# msx_io_expander_slot.net
KiCad netlist of a schematic drawn in EAGLE
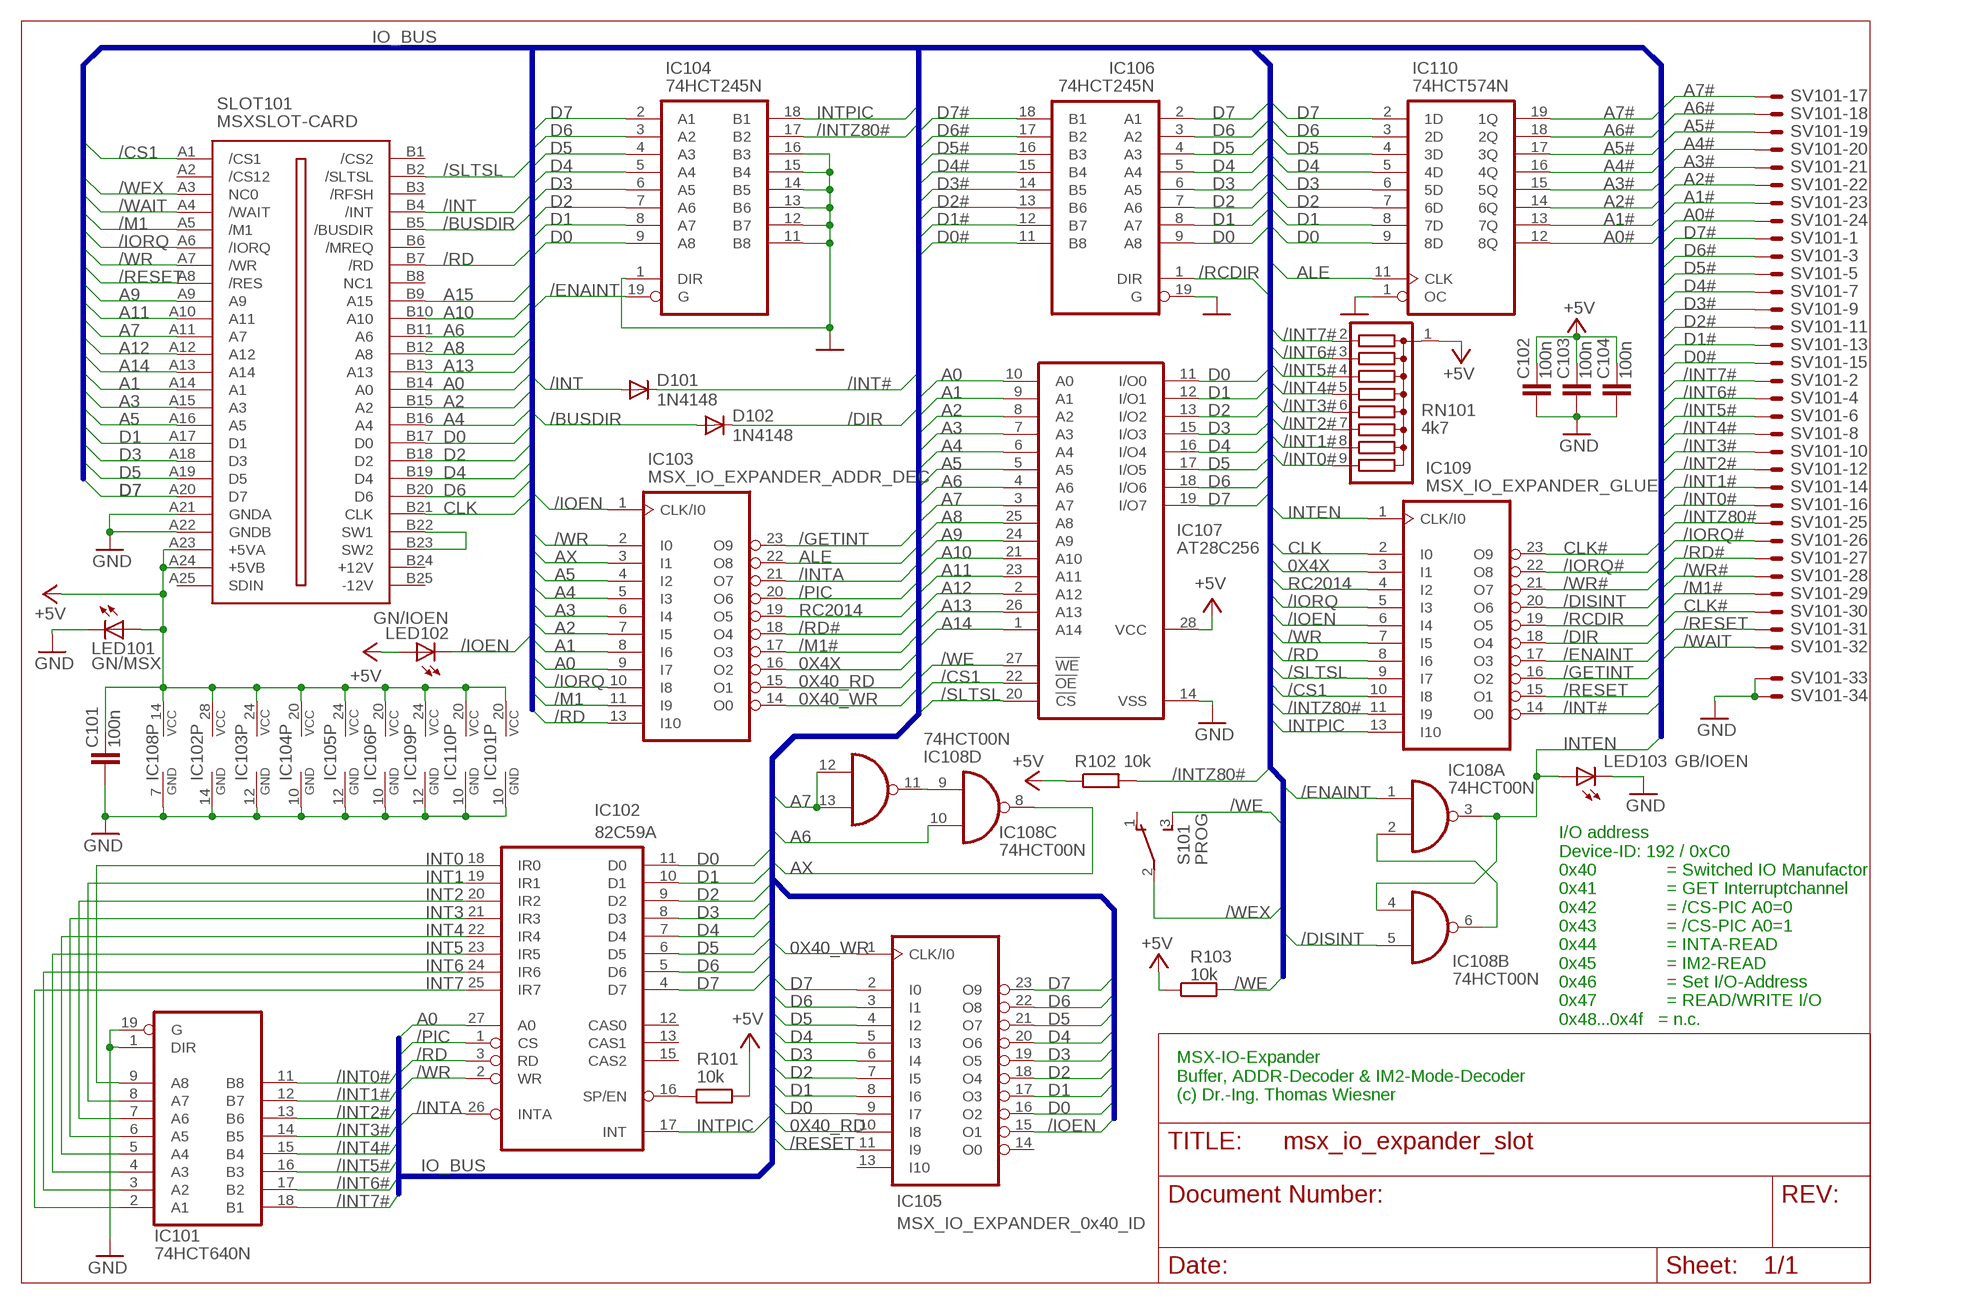
[diagram p0: schematic, sheet 1]

(export (version "E")
  (design (tool "Eeschema 10.0.6"))
  (components
    (comp (ref "C101")
      (value "100n")
      (footprint "eagle-import:C025-025X050")
      (libsource (lib "eagle-import") (part "C-EU025-025X050"))
    )
    (comp (ref "C102")
      (value "100n")
      (footprint "eagle-import:C025-025X050")
      (libsource (lib "eagle-import") (part "C-EU025-025X050"))
    )
    (comp (ref "C103")
      (value "100n")
      (footprint "eagle-import:C025-025X050")
      (libsource (lib "eagle-import") (part "C-EU025-025X050"))
    )
    (comp (ref "C104")
      (value "100n")
      (footprint "eagle-import:C025-025X050")
      (libsource (lib "eagle-import") (part "C-EU025-025X050"))
    )
    (comp (ref "D101")
      (value "1N4148")
      (footprint "eagle-import:DO35-10")
      (libsource (lib "eagle-import") (part "1N4148DO35-10"))
    )
    (comp (ref "D102")
      (value "1N4148")
      (footprint "eagle-import:DO35-10")
      (libsource (lib "eagle-import") (part "1N4148DO35-10"))
    )
    (comp (ref "IC101")
      (value "74HCT640N")
      (footprint "eagle-import:DIL20")
      (libsource (lib "eagle-import") (part "74245NHCT"))
    )
    (comp (ref "IC102")
      (value "82C59A")
      (footprint "eagle-import:DIL28-6")
      (libsource (lib "eagle-import") (part "8259A"))
    )
    (comp (ref "IC103")
      (value "MSX_IO_EXPANDER_ADDR_DEC")
      (footprint "eagle-import:DIL24-3")
      (fields (field (name "MPN") "GAL22V10D-7LPN"))
      (libsource (lib "eagle-import") (part "22V10"))
    )
    (comp (ref "IC104")
      (value "74HCT245N")
      (footprint "eagle-import:DIL20")
      (libsource (lib "eagle-import") (part "74245NHCT"))
    )
    (comp (ref "IC105")
      (value "MSX_IO_EXPANDER_0x40_ID")
      (footprint "eagle-import:DIL24-3")
      (fields (field (name "MPN") "GAL22V10D-7LPN"))
      (libsource (lib "eagle-import") (part "22V10"))
    )
    (comp (ref "IC106")
      (value "74HCT245N")
      (footprint "eagle-import:DIL20")
      (libsource (lib "eagle-import") (part "74245NHCT"))
    )
    (comp (ref "IC107")
      (value "AT28C256")
      (footprint "eagle-import:DIL28-6")
      (libsource (lib "eagle-import") (part "62256P"))
    )
    (comp (ref "IC108")
      (value "74HCT00N")
      (footprint "eagle-import:DIL14")
      (libsource (lib "eagle-import") (part "7400NHCT"))
    )
    (comp (ref "IC109")
      (value "MSX_IO_EXPANDER_GLUE")
      (footprint "eagle-import:DIL24-3")
      (fields (field (name "MPN") "GAL22V10D-7LPN"))
      (libsource (lib "eagle-import") (part "22V10"))
    )
    (comp (ref "IC110")
      (value "74HCT574N")
      (footprint "eagle-import:DIL20")
      (libsource (lib "eagle-import") (part "74574NHCT"))
    )
    (comp (ref "LED101")
      (value "GN/MSX")
      (footprint "eagle-import:LED3MM")
      (libsource (lib "eagle-import") (part "LED3MM"))
    )
    (comp (ref "LED102")
      (value "GN/IOEN")
      (footprint "eagle-import:LED3MM")
      (libsource (lib "eagle-import") (part "LED3MM"))
    )
    (comp (ref "LED103")
      (value "GB/IOEN")
      (footprint "eagle-import:LED3MM")
      (libsource (lib "eagle-import") (part "LED3MM"))
    )
    (comp (ref "R101")
      (value "10k")
      (footprint "eagle-import:0207_10")
      (libsource (lib "eagle-import") (part "R-EU_0207/10"))
    )
    (comp (ref "R102")
      (value "10k")
      (footprint "eagle-import:0207_10")
      (libsource (lib "eagle-import") (part "R-EU_0207/10"))
    )
    (comp (ref "R103")
      (value "10k")
      (footprint "eagle-import:0207_10")
      (libsource (lib "eagle-import") (part "R-EU_0207/10"))
    )
    (comp (ref "RN101")
      (value "4k7")
      (footprint "eagle-import:SIL9")
      (libsource (lib "eagle-import") (part "G08R"))
    )
    (comp (ref "S101")
      (value "PROG")
      (footprint "eagle-import:TL3XPO")
      (libsource (lib "eagle-import") (part "TL36PO"))
    )
    (comp (ref "SLOT101")
      (value "MSXSLOT-CARD")
      (footprint "eagle-import:MSXCARD")
      (libsource (lib "eagle-import") (part "MSXSLOT-CARD"))
    )
    (comp (ref "SV101")
      (value "ML343MLE")
      (footprint "eagle-import:3M_34L")
      (libsource (lib "eagle-import") (part "ML34?E3ML"))
    )
  )
  (nets
    (net (code "2") (name "+5V") (class "Default")
      (node (ref "C101") (pin "2") (pinfunction "2_2") (pintype "passive"))
      (node (ref "C102") (pin "2") (pinfunction "2_2") (pintype "passive"))
      (node (ref "C103") (pin "2") (pinfunction "2_2") (pintype "passive"))
      (node (ref "C104") (pin "2") (pinfunction "2_2") (pintype "passive"))
      (node (ref "IC101") (pin "20") (pinfunction "VCC_20") (pintype "power_in"))
      (node (ref "IC102") (pin "28") (pinfunction "VCC_28") (pintype "power_in"))
      (node (ref "IC103") (pin "24") (pinfunction "VCC_24") (pintype "power_in"))
      (node (ref "IC104") (pin "20") (pinfunction "VCC_20") (pintype "power_in"))
      (node (ref "IC105") (pin "24") (pinfunction "VCC_24") (pintype "power_in"))
      (node (ref "IC106") (pin "20") (pinfunction "VCC_20") (pintype "power_in"))
      (node (ref "IC107") (pin "28") (pinfunction "VCC_28") (pintype "power_in"))
      (node (ref "IC108") (pin "14") (pinfunction "VCC_14") (pintype "power_in"))
      (node (ref "IC109") (pin "24") (pinfunction "VCC_24") (pintype "power_in"))
      (node (ref "IC110") (pin "20") (pinfunction "VCC_20") (pintype "power_in"))
      (node (ref "LED101") (pin "A") (pinfunction "A_A") (pintype "passive"))
      (node (ref "LED102") (pin "A") (pinfunction "A_A") (pintype "passive"))
      (node (ref "R101") (pin "2") (pinfunction "2_2") (pintype "passive"))
      (node (ref "R102") (pin "1") (pinfunction "1_1") (pintype "passive"))
      (node (ref "R103") (pin "1") (pinfunction "1_1") (pintype "passive"))
      (node (ref "RN101") (pin "1") (pinfunction "1_1") (pintype "passive"))
      (node (ref "SLOT101") (pin "A23") (pinfunction "+5VA_A23") (pintype "bidirectional"))
      (node (ref "SLOT101") (pin "A24") (pinfunction "+5VB_A24") (pintype "bidirectional"))
    )
    (net (code "3") (name "/0X4X") (class "Default")
      (node (ref "IC103") (pin "16") (pinfunction "O2_16") (pintype "bidirectional"))
      (node (ref "IC109") (pin "3") (pinfunction "I1_3") (pintype "input"))
    )
    (net (code "4") (name "/0X40_RD") (class "Default")
      (node (ref "IC103") (pin "15") (pinfunction "O1_15") (pintype "bidirectional"))
      (node (ref "IC105") (pin "10") (pinfunction "I8_10") (pintype "input"))
    )
    (net (code "5") (name "/0X40_WR") (class "Default")
      (node (ref "IC103") (pin "14") (pinfunction "O0_14") (pintype "bidirectional"))
      (node (ref "IC105") (pin "1") (pinfunction "CLK/I0_1") (pintype "input"))
    )
    (net (code "6") (name "/A0") (class "Default")
      (node (ref "IC102") (pin "27") (pinfunction "A0_27") (pintype "input"))
      (node (ref "IC103") (pin "9") (pinfunction "I7_9") (pintype "input"))
      (node (ref "IC107") (pin "10") (pinfunction "A0_10") (pintype "input"))
      (node (ref "SLOT101") (pin "B14") (pinfunction "A0_B14") (pintype "bidirectional"))
    )
    (net (code "7") (name "/A0#") (class "Default")
      (node (ref "IC110") (pin "12") (pinfunction "8Q_12") (pintype "tri_state"))
      (node (ref "SV101") (pin "24") (pinfunction "S_24") (pintype "passive"))
    )
    (net (code "8") (name "/A1") (class "Default")
      (node (ref "IC103") (pin "8") (pinfunction "I6_8") (pintype "input"))
      (node (ref "IC107") (pin "9") (pinfunction "A1_9") (pintype "input"))
      (node (ref "SLOT101") (pin "A14") (pinfunction "A1_A14") (pintype "bidirectional"))
    )
    (net (code "9") (name "/A1#") (class "Default")
      (node (ref "IC110") (pin "13") (pinfunction "7Q_13") (pintype "tri_state"))
      (node (ref "SV101") (pin "23") (pinfunction "S_23") (pintype "passive"))
    )
    (net (code "10") (name "/A2") (class "Default")
      (node (ref "IC103") (pin "7") (pinfunction "I5_7") (pintype "input"))
      (node (ref "IC107") (pin "8") (pinfunction "A2_8") (pintype "input"))
      (node (ref "SLOT101") (pin "B15") (pinfunction "A2_B15") (pintype "bidirectional"))
    )
    (net (code "11") (name "/A2#") (class "Default")
      (node (ref "IC110") (pin "14") (pinfunction "6Q_14") (pintype "tri_state"))
      (node (ref "SV101") (pin "22") (pinfunction "S_22") (pintype "passive"))
    )
    (net (code "12") (name "/A3") (class "Default")
      (node (ref "IC103") (pin "6") (pinfunction "I4_6") (pintype "input"))
      (node (ref "IC107") (pin "7") (pinfunction "A3_7") (pintype "input"))
      (node (ref "SLOT101") (pin "A15") (pinfunction "A3_A15") (pintype "bidirectional"))
    )
    (net (code "13") (name "/A3#") (class "Default")
      (node (ref "IC110") (pin "15") (pinfunction "5Q_15") (pintype "tri_state"))
      (node (ref "SV101") (pin "21") (pinfunction "S_21") (pintype "passive"))
    )
    (net (code "14") (name "/A4") (class "Default")
      (node (ref "IC103") (pin "5") (pinfunction "I3_5") (pintype "input"))
      (node (ref "IC107") (pin "6") (pinfunction "A4_6") (pintype "input"))
      (node (ref "SLOT101") (pin "B16") (pinfunction "A4_B16") (pintype "bidirectional"))
    )
    (net (code "15") (name "/A4#") (class "Default")
      (node (ref "IC110") (pin "16") (pinfunction "4Q_16") (pintype "tri_state"))
      (node (ref "SV101") (pin "20") (pinfunction "S_20") (pintype "passive"))
    )
    (net (code "16") (name "/A5") (class "Default")
      (node (ref "IC103") (pin "4") (pinfunction "I2_4") (pintype "input"))
      (node (ref "IC107") (pin "5") (pinfunction "A5_5") (pintype "input"))
      (node (ref "SLOT101") (pin "A16") (pinfunction "A5_A16") (pintype "bidirectional"))
    )
    (net (code "17") (name "/A5#") (class "Default")
      (node (ref "IC110") (pin "17") (pinfunction "3Q_17") (pintype "tri_state"))
      (node (ref "SV101") (pin "19") (pinfunction "S_19") (pintype "passive"))
    )
    (net (code "18") (name "/A6") (class "Default")
      (node (ref "IC107") (pin "4") (pinfunction "A6_4") (pintype "input"))
      (node (ref "IC108") (pin "10") (pinfunction "I1_10") (pintype "input"))
      (node (ref "SLOT101") (pin "B11") (pinfunction "A6_B11") (pintype "bidirectional"))
    )
    (net (code "19") (name "/A6#") (class "Default")
      (node (ref "IC110") (pin "18") (pinfunction "2Q_18") (pintype "tri_state"))
      (node (ref "SV101") (pin "18") (pinfunction "S_18") (pintype "passive"))
    )
    (net (code "20") (name "/A7") (class "Default")
      (node (ref "IC107") (pin "3") (pinfunction "A7_3") (pintype "input"))
      (node (ref "IC108") (pin "12") (pinfunction "I0_12") (pintype "input"))
      (node (ref "IC108") (pin "13") (pinfunction "I1_13") (pintype "input"))
      (node (ref "SLOT101") (pin "A11") (pinfunction "A7_A11") (pintype "bidirectional"))
    )
    (net (code "21") (name "/A7#") (class "Default")
      (node (ref "IC110") (pin "19") (pinfunction "1Q_19") (pintype "tri_state"))
      (node (ref "SV101") (pin "17") (pinfunction "S_17") (pintype "passive"))
    )
    (net (code "22") (name "/A8") (class "Default")
      (node (ref "IC107") (pin "25") (pinfunction "A8_25") (pintype "input"))
      (node (ref "SLOT101") (pin "B12") (pinfunction "A8_B12") (pintype "bidirectional"))
    )
    (net (code "23") (name "/A9") (class "Default")
      (node (ref "IC107") (pin "24") (pinfunction "A9_24") (pintype "input"))
      (node (ref "SLOT101") (pin "A9") (pinfunction "A9_A9") (pintype "bidirectional"))
    )
    (net (code "24") (name "/A10") (class "Default")
      (node (ref "IC107") (pin "21") (pinfunction "A10_21") (pintype "input"))
      (node (ref "SLOT101") (pin "B10") (pinfunction "A10_B10") (pintype "bidirectional"))
    )
    (net (code "25") (name "/A11") (class "Default")
      (node (ref "IC107") (pin "23") (pinfunction "A11_23") (pintype "input"))
      (node (ref "SLOT101") (pin "A10") (pinfunction "A11_A10") (pintype "bidirectional"))
    )
    (net (code "26") (name "/A12") (class "Default")
      (node (ref "IC107") (pin "2") (pinfunction "A12_2") (pintype "input"))
      (node (ref "SLOT101") (pin "A12") (pinfunction "A12_A12") (pintype "bidirectional"))
    )
    (net (code "27") (name "/A13") (class "Default")
      (node (ref "IC107") (pin "26") (pinfunction "A13_26") (pintype "input"))
      (node (ref "SLOT101") (pin "B13") (pinfunction "A13_B13") (pintype "bidirectional"))
    )
    (net (code "28") (name "/A14") (class "Default")
      (node (ref "IC107") (pin "1") (pinfunction "A14_1") (pintype "input"))
      (node (ref "SLOT101") (pin "A13") (pinfunction "A14_A13") (pintype "bidirectional"))
    )
    (net (code "29") (name "/A15") (class "Default")
      (node (ref "SLOT101") (pin "B9") (pinfunction "A15_B9") (pintype "bidirectional"))
    )
    (net (code "30") (name "/ALE") (class "Default")
      (node (ref "IC103") (pin "22") (pinfunction "O8_22") (pintype "bidirectional"))
      (node (ref "IC110") (pin "11") (pinfunction "CLK_11") (pintype "input"))
    )
    (net (code "31") (name "/AX") (class "Default")
      (node (ref "IC103") (pin "3") (pinfunction "I1_3") (pintype "input"))
      (node (ref "IC108") (pin "8") (pinfunction "O_8") (pintype "output"))
    )
    (net (code "32") (name "/CLK") (class "Default")
      (node (ref "IC109") (pin "2") (pinfunction "I0_2") (pintype "input"))
      (node (ref "SLOT101") (pin "B21") (pinfunction "CLK_B21") (pintype "bidirectional"))
    )
    (net (code "33") (name "/CLK#") (class "Default")
      (node (ref "IC109") (pin "23") (pinfunction "O9_23") (pintype "bidirectional"))
      (node (ref "SV101") (pin "30") (pinfunction "S_30") (pintype "passive"))
    )
    (net (code "34") (name "/D0") (class "Default")
      (node (ref "IC102") (pin "11") (pinfunction "D0_11") (pintype "bidirectional"))
      (node (ref "IC104") (pin "9") (pinfunction "A8_9") (pintype "bidirectional"))
      (node (ref "IC105") (pin "16") (pinfunction "O2_16") (pintype "bidirectional"))
      (node (ref "IC105") (pin "9") (pinfunction "I7_9") (pintype "input"))
      (node (ref "IC106") (pin "9") (pinfunction "A8_9") (pintype "bidirectional"))
      (node (ref "IC107") (pin "11") (pinfunction "I/O0_11") (pintype "bidirectional"))
      (node (ref "IC110") (pin "9") (pinfunction "8D_9") (pintype "input"))
      (node (ref "SLOT101") (pin "B17") (pinfunction "D0_B17") (pintype "bidirectional"))
    )
    (net (code "35") (name "/D0#") (class "Default")
      (node (ref "IC106") (pin "11") (pinfunction "B8_11") (pintype "bidirectional"))
      (node (ref "SV101") (pin "15") (pinfunction "S_15") (pintype "passive"))
    )
    (net (code "36") (name "/D1") (class "Default")
      (node (ref "IC102") (pin "10") (pinfunction "D1_10") (pintype "bidirectional"))
      (node (ref "IC104") (pin "8") (pinfunction "A7_8") (pintype "bidirectional"))
      (node (ref "IC105") (pin "17") (pinfunction "O3_17") (pintype "bidirectional"))
      (node (ref "IC105") (pin "8") (pinfunction "I6_8") (pintype "input"))
      (node (ref "IC106") (pin "8") (pinfunction "A7_8") (pintype "bidirectional"))
      (node (ref "IC107") (pin "12") (pinfunction "I/O1_12") (pintype "bidirectional"))
      (node (ref "IC110") (pin "8") (pinfunction "7D_8") (pintype "input"))
      (node (ref "SLOT101") (pin "A17") (pinfunction "D1_A17") (pintype "bidirectional"))
    )
    (net (code "37") (name "/D1#") (class "Default")
      (node (ref "IC106") (pin "12") (pinfunction "B7_12") (pintype "bidirectional"))
      (node (ref "SV101") (pin "13") (pinfunction "S_13") (pintype "passive"))
    )
    (net (code "38") (name "/D2") (class "Default")
      (node (ref "IC102") (pin "9") (pinfunction "D2_9") (pintype "bidirectional"))
      (node (ref "IC104") (pin "7") (pinfunction "A6_7") (pintype "bidirectional"))
      (node (ref "IC105") (pin "18") (pinfunction "O4_18") (pintype "bidirectional"))
      (node (ref "IC105") (pin "7") (pinfunction "I5_7") (pintype "input"))
      (node (ref "IC106") (pin "7") (pinfunction "A6_7") (pintype "bidirectional"))
      (node (ref "IC107") (pin "13") (pinfunction "I/O2_13") (pintype "bidirectional"))
      (node (ref "IC110") (pin "7") (pinfunction "6D_7") (pintype "input"))
      (node (ref "SLOT101") (pin "B18") (pinfunction "D2_B18") (pintype "bidirectional"))
    )
    (net (code "39") (name "/D2#") (class "Default")
      (node (ref "IC106") (pin "13") (pinfunction "B6_13") (pintype "bidirectional"))
      (node (ref "SV101") (pin "11") (pinfunction "S_11") (pintype "passive"))
    )
    (net (code "40") (name "/D3") (class "Default")
      (node (ref "IC102") (pin "8") (pinfunction "D3_8") (pintype "bidirectional"))
      (node (ref "IC104") (pin "6") (pinfunction "A5_6") (pintype "bidirectional"))
      (node (ref "IC105") (pin "19") (pinfunction "O5_19") (pintype "bidirectional"))
      (node (ref "IC105") (pin "6") (pinfunction "I4_6") (pintype "input"))
      (node (ref "IC106") (pin "6") (pinfunction "A5_6") (pintype "bidirectional"))
      (node (ref "IC107") (pin "15") (pinfunction "I/O3_15") (pintype "bidirectional"))
      (node (ref "IC110") (pin "6") (pinfunction "5D_6") (pintype "input"))
      (node (ref "SLOT101") (pin "A18") (pinfunction "D3_A18") (pintype "bidirectional"))
    )
    (net (code "41") (name "/D3#") (class "Default")
      (node (ref "IC106") (pin "14") (pinfunction "B5_14") (pintype "bidirectional"))
      (node (ref "SV101") (pin "9") (pinfunction "S_9") (pintype "passive"))
    )
    (net (code "42") (name "/D4") (class "Default")
      (node (ref "IC102") (pin "7") (pinfunction "D4_7") (pintype "bidirectional"))
      (node (ref "IC104") (pin "5") (pinfunction "A4_5") (pintype "bidirectional"))
      (node (ref "IC105") (pin "20") (pinfunction "O6_20") (pintype "bidirectional"))
      (node (ref "IC105") (pin "5") (pinfunction "I3_5") (pintype "input"))
      (node (ref "IC106") (pin "5") (pinfunction "A4_5") (pintype "bidirectional"))
      (node (ref "IC107") (pin "16") (pinfunction "I/O4_16") (pintype "bidirectional"))
      (node (ref "IC110") (pin "5") (pinfunction "4D_5") (pintype "input"))
      (node (ref "SLOT101") (pin "B19") (pinfunction "D4_B19") (pintype "bidirectional"))
    )
    (net (code "43") (name "/D4#") (class "Default")
      (node (ref "IC106") (pin "15") (pinfunction "B4_15") (pintype "bidirectional"))
      (node (ref "SV101") (pin "7") (pinfunction "S_7") (pintype "passive"))
    )
    (net (code "44") (name "/D5") (class "Default")
      (node (ref "IC102") (pin "6") (pinfunction "D5_6") (pintype "bidirectional"))
      (node (ref "IC104") (pin "4") (pinfunction "A3_4") (pintype "bidirectional"))
      (node (ref "IC105") (pin "21") (pinfunction "O7_21") (pintype "bidirectional"))
      (node (ref "IC105") (pin "4") (pinfunction "I2_4") (pintype "input"))
      (node (ref "IC106") (pin "4") (pinfunction "A3_4") (pintype "bidirectional"))
      (node (ref "IC107") (pin "17") (pinfunction "I/O5_17") (pintype "bidirectional"))
      (node (ref "IC110") (pin "4") (pinfunction "3D_4") (pintype "input"))
      (node (ref "SLOT101") (pin "A19") (pinfunction "D5_A19") (pintype "bidirectional"))
    )
    (net (code "45") (name "/D5#") (class "Default")
      (node (ref "IC106") (pin "16") (pinfunction "B3_16") (pintype "bidirectional"))
      (node (ref "SV101") (pin "5") (pinfunction "S_5") (pintype "passive"))
    )
    (net (code "46") (name "/D6") (class "Default")
      (node (ref "IC102") (pin "5") (pinfunction "D6_5") (pintype "bidirectional"))
      (node (ref "IC104") (pin "3") (pinfunction "A2_3") (pintype "bidirectional"))
      (node (ref "IC105") (pin "22") (pinfunction "O8_22") (pintype "bidirectional"))
      (node (ref "IC105") (pin "3") (pinfunction "I1_3") (pintype "input"))
      (node (ref "IC106") (pin "3") (pinfunction "A2_3") (pintype "bidirectional"))
      (node (ref "IC107") (pin "18") (pinfunction "I/O6_18") (pintype "bidirectional"))
      (node (ref "IC110") (pin "3") (pinfunction "2D_3") (pintype "input"))
      (node (ref "SLOT101") (pin "B20") (pinfunction "D6_B20") (pintype "bidirectional"))
    )
    (net (code "47") (name "/D6#") (class "Default")
      (node (ref "IC106") (pin "17") (pinfunction "B2_17") (pintype "bidirectional"))
      (node (ref "SV101") (pin "3") (pinfunction "S_3") (pintype "passive"))
    )
    (net (code "48") (name "/D7") (class "Default")
      (node (ref "IC102") (pin "4") (pinfunction "D7_4") (pintype "bidirectional"))
      (node (ref "IC104") (pin "2") (pinfunction "A1_2") (pintype "bidirectional"))
      (node (ref "IC105") (pin "2") (pinfunction "I0_2") (pintype "input"))
      (node (ref "IC105") (pin "23") (pinfunction "O9_23") (pintype "bidirectional"))
      (node (ref "IC106") (pin "2") (pinfunction "A1_2") (pintype "bidirectional"))
      (node (ref "IC107") (pin "19") (pinfunction "I/O7_19") (pintype "bidirectional"))
      (node (ref "IC110") (pin "2") (pinfunction "1D_2") (pintype "input"))
      (node (ref "SLOT101") (pin "A20") (pinfunction "D7_A20") (pintype "bidirectional"))
    )
    (net (code "49") (name "/D7#") (class "Default")
      (node (ref "IC106") (pin "18") (pinfunction "B1_18") (pintype "bidirectional"))
      (node (ref "SV101") (pin "1") (pinfunction "S_1") (pintype "passive"))
    )
    (net (code "50") (name "/INT0") (class "Default")
      (node (ref "IC101") (pin "9") (pinfunction "A8_9") (pintype "bidirectional"))
      (node (ref "IC102") (pin "18") (pinfunction "IR0_18") (pintype "input"))
    )
    (net (code "51") (name "/INT1") (class "Default")
      (node (ref "IC101") (pin "8") (pinfunction "A7_8") (pintype "bidirectional"))
      (node (ref "IC102") (pin "19") (pinfunction "IR1_19") (pintype "input"))
    )
    (net (code "52") (name "/INT2") (class "Default")
      (node (ref "IC101") (pin "7") (pinfunction "A6_7") (pintype "bidirectional"))
      (node (ref "IC102") (pin "20") (pinfunction "IR2_20") (pintype "input"))
    )
    (net (code "53") (name "/INT3") (class "Default")
      (node (ref "IC101") (pin "6") (pinfunction "A5_6") (pintype "bidirectional"))
      (node (ref "IC102") (pin "21") (pinfunction "IR3_21") (pintype "input"))
    )
    (net (code "54") (name "/INT4") (class "Default")
      (node (ref "IC101") (pin "5") (pinfunction "A4_5") (pintype "bidirectional"))
      (node (ref "IC102") (pin "22") (pinfunction "IR4_22") (pintype "input"))
    )
    (net (code "55") (name "/INT5") (class "Default")
      (node (ref "IC101") (pin "4") (pinfunction "A3_4") (pintype "bidirectional"))
      (node (ref "IC102") (pin "23") (pinfunction "IR5_23") (pintype "input"))
    )
    (net (code "56") (name "/INT6") (class "Default")
      (node (ref "IC101") (pin "3") (pinfunction "A2_3") (pintype "bidirectional"))
      (node (ref "IC102") (pin "24") (pinfunction "IR6_24") (pintype "input"))
    )
    (net (code "57") (name "/INT7") (class "Default")
      (node (ref "IC101") (pin "2") (pinfunction "A1_2") (pintype "bidirectional"))
      (node (ref "IC102") (pin "25") (pinfunction "IR7_25") (pintype "input"))
    )
    (net (code "58") (name "/INTEN") (class "Default")
      (node (ref "IC108") (pin "3") (pinfunction "O_3") (pintype "output"))
      (node (ref "IC108") (pin "4") (pinfunction "I0_4") (pintype "input"))
      (node (ref "IC109") (pin "1") (pinfunction "CLK/I0_1") (pintype "input"))
      (node (ref "LED103") (pin "A") (pinfunction "A_A") (pintype "passive"))
    )
    (net (code "59") (name "/INTPIC") (class "Default")
      (node (ref "IC102") (pin "17") (pinfunction "INT_17") (pintype "output"))
      (node (ref "IC104") (pin "18") (pinfunction "B1_18") (pintype "bidirectional"))
      (node (ref "IC109") (pin "13") (pinfunction "I10_13") (pintype "input"))
    )
    (net (code "60") (name "/RC2014") (class "Default")
      (node (ref "IC103") (pin "19") (pinfunction "O5_19") (pintype "bidirectional"))
      (node (ref "IC109") (pin "4") (pinfunction "I2_4") (pintype "input"))
    )
    (net (code "62") (name "/{slash}BUSDIR") (class "Default")
      (node (ref "D102") (pin "A") (pinfunction "A_A") (pintype "passive"))
      (node (ref "SLOT101") (pin "B5") (pinfunction "/BUSDIR_B5") (pintype "bidirectional"))
    )
    (net (code "63") (name "/{slash}CS1") (class "Default")
      (node (ref "IC107") (pin "22") (pinfunction "~{OE}_22") (pintype "input"))
      (node (ref "IC109") (pin "10") (pinfunction "I8_10") (pintype "input"))
      (node (ref "SLOT101") (pin "A1") (pinfunction "/CS1_A1") (pintype "bidirectional"))
    )
    (net (code "64") (name "/{slash}DIR") (class "Default")
      (node (ref "D102") (pin "C") (pinfunction "C_C") (pintype "passive"))
      (node (ref "IC109") (pin "18") (pinfunction "O4_18") (pintype "bidirectional"))
    )
    (net (code "65") (name "/{slash}DISINT") (class "Default")
      (node (ref "IC108") (pin "5") (pinfunction "I1_5") (pintype "input"))
      (node (ref "IC109") (pin "20") (pinfunction "O6_20") (pintype "bidirectional"))
    )
    (net (code "66") (name "/{slash}ENAINT") (class "Default")
      (node (ref "IC104") (pin "19") (pinfunction "G_19") (pintype "input"))
      (node (ref "IC108") (pin "1") (pinfunction "I0_1") (pintype "input"))
      (node (ref "IC109") (pin "17") (pinfunction "O3_17") (pintype "bidirectional"))
    )
    (net (code "67") (name "/{slash}GETINT") (class "Default")
      (node (ref "IC103") (pin "23") (pinfunction "O9_23") (pintype "bidirectional"))
      (node (ref "IC109") (pin "16") (pinfunction "O2_16") (pintype "bidirectional"))
    )
    (net (code "68") (name "/{slash}INT") (class "Default")
      (node (ref "D101") (pin "A") (pinfunction "A_A") (pintype "passive"))
      (node (ref "SLOT101") (pin "B4") (pinfunction "/INT_B4") (pintype "bidirectional"))
    )
    (net (code "69") (name "/{slash}INT#") (class "Default")
      (node (ref "D101") (pin "C") (pinfunction "C_C") (pintype "passive"))
      (node (ref "IC109") (pin "14") (pinfunction "O0_14") (pintype "bidirectional"))
    )
    (net (code "70") (name "/{slash}INT0#") (class "Default")
      (node (ref "IC101") (pin "11") (pinfunction "B8_11") (pintype "bidirectional"))
      (node (ref "RN101") (pin "9") (pinfunction "9_9") (pintype "passive"))
      (node (ref "SV101") (pin "16") (pinfunction "S_16") (pintype "passive"))
    )
    (net (code "71") (name "/{slash}INT1#") (class "Default")
      (node (ref "IC101") (pin "12") (pinfunction "B7_12") (pintype "bidirectional"))
      (node (ref "RN101") (pin "8") (pinfunction "8_8") (pintype "passive"))
      (node (ref "SV101") (pin "14") (pinfunction "S_14") (pintype "passive"))
    )
    (net (code "72") (name "/{slash}INT2#") (class "Default")
      (node (ref "IC101") (pin "13") (pinfunction "B6_13") (pintype "bidirectional"))
      (node (ref "RN101") (pin "7") (pinfunction "7_7") (pintype "passive"))
      (node (ref "SV101") (pin "12") (pinfunction "S_12") (pintype "passive"))
    )
    (net (code "73") (name "/{slash}INT3#") (class "Default")
      (node (ref "IC101") (pin "14") (pinfunction "B5_14") (pintype "bidirectional"))
      (node (ref "RN101") (pin "6") (pinfunction "6_6") (pintype "passive"))
      (node (ref "SV101") (pin "10") (pinfunction "S_10") (pintype "passive"))
    )
    (net (code "74") (name "/{slash}INT4#") (class "Default")
      (node (ref "IC101") (pin "15") (pinfunction "B4_15") (pintype "bidirectional"))
      (node (ref "RN101") (pin "5") (pinfunction "5_5") (pintype "passive"))
      (node (ref "SV101") (pin "8") (pinfunction "S_8") (pintype "passive"))
    )
    (net (code "75") (name "/{slash}INT5#") (class "Default")
      (node (ref "IC101") (pin "16") (pinfunction "B3_16") (pintype "bidirectional"))
      (node (ref "RN101") (pin "4") (pinfunction "4_4") (pintype "passive"))
      (node (ref "SV101") (pin "6") (pinfunction "S_6") (pintype "passive"))
    )
    (net (code "76") (name "/{slash}INT6#") (class "Default")
      (node (ref "IC101") (pin "17") (pinfunction "B2_17") (pintype "bidirectional"))
      (node (ref "RN101") (pin "3") (pinfunction "3_3") (pintype "passive"))
      (node (ref "SV101") (pin "4") (pinfunction "S_4") (pintype "passive"))
    )
    (net (code "77") (name "/{slash}INT7#") (class "Default")
      (node (ref "IC101") (pin "18") (pinfunction "B1_18") (pintype "bidirectional"))
      (node (ref "RN101") (pin "2") (pinfunction "2_2") (pintype "passive"))
      (node (ref "SV101") (pin "2") (pinfunction "S_2") (pintype "passive"))
    )
    (net (code "78") (name "/{slash}INTA") (class "Default")
      (node (ref "IC102") (pin "26") (pinfunction "INTA_26") (pintype "input"))
      (node (ref "IC103") (pin "21") (pinfunction "O7_21") (pintype "bidirectional"))
    )
    (net (code "79") (name "/{slash}INTZ80#") (class "Default")
      (node (ref "IC104") (pin "17") (pinfunction "B2_17") (pintype "bidirectional"))
      (node (ref "IC109") (pin "11") (pinfunction "I9_11") (pintype "input"))
      (node (ref "R102") (pin "2") (pinfunction "2_2") (pintype "passive"))
      (node (ref "SV101") (pin "25") (pinfunction "S_25") (pintype "passive"))
    )
    (net (code "80") (name "/{slash}IOEN") (class "Default")
      (node (ref "IC103") (pin "1") (pinfunction "CLK/I0_1") (pintype "input"))
      (node (ref "IC105") (pin "15") (pinfunction "O1_15") (pintype "bidirectional"))
      (node (ref "IC109") (pin "6") (pinfunction "I4_6") (pintype "input"))
      (node (ref "LED102") (pin "K") (pinfunction "C_K") (pintype "passive"))
    )
    (net (code "81") (name "/{slash}IORQ") (class "Default")
      (node (ref "IC103") (pin "10") (pinfunction "I8_10") (pintype "input"))
      (node (ref "IC109") (pin "5") (pinfunction "I3_5") (pintype "input"))
      (node (ref "SLOT101") (pin "A6") (pinfunction "/IORQ_A6") (pintype "bidirectional"))
    )
    (net (code "82") (name "/{slash}IORQ#") (class "Default")
      (node (ref "IC109") (pin "22") (pinfunction "O8_22") (pintype "bidirectional"))
      (node (ref "SV101") (pin "26") (pinfunction "S_26") (pintype "passive"))
    )
    (net (code "83") (name "/{slash}M1") (class "Default")
      (node (ref "IC103") (pin "11") (pinfunction "I9_11") (pintype "input"))
      (node (ref "SLOT101") (pin "A5") (pinfunction "/M1_A5") (pintype "bidirectional"))
    )
    (net (code "84") (name "/{slash}M1#") (class "Default")
      (node (ref "IC103") (pin "17") (pinfunction "O3_17") (pintype "bidirectional"))
      (node (ref "SV101") (pin "29") (pinfunction "S_29") (pintype "passive"))
    )
    (net (code "85") (name "/{slash}PIC") (class "Default")
      (node (ref "IC102") (pin "1") (pinfunction "CS_1") (pintype "input"))
      (node (ref "IC103") (pin "20") (pinfunction "O6_20") (pintype "bidirectional"))
    )
    (net (code "86") (name "/{slash}RCDIR") (class "Default")
      (node (ref "IC106") (pin "1") (pinfunction "DIR_1") (pintype "input"))
      (node (ref "IC109") (pin "19") (pinfunction "O5_19") (pintype "bidirectional"))
    )
    (net (code "87") (name "/{slash}RD") (class "Default")
      (node (ref "IC102") (pin "3") (pinfunction "RD_3") (pintype "input"))
      (node (ref "IC103") (pin "13") (pinfunction "I10_13") (pintype "input"))
      (node (ref "IC109") (pin "8") (pinfunction "I6_8") (pintype "input"))
      (node (ref "SLOT101") (pin "B7") (pinfunction "/RD_B7") (pintype "bidirectional"))
    )
    (net (code "88") (name "/{slash}RD#") (class "Default")
      (node (ref "IC103") (pin "18") (pinfunction "O4_18") (pintype "bidirectional"))
      (node (ref "SV101") (pin "27") (pinfunction "S_27") (pintype "passive"))
    )
    (net (code "89") (name "/{slash}RESET") (class "Default")
      (node (ref "IC105") (pin "11") (pinfunction "I9_11") (pintype "input"))
      (node (ref "IC109") (pin "15") (pinfunction "O1_15") (pintype "bidirectional"))
      (node (ref "SLOT101") (pin "A8") (pinfunction "/RES_A8") (pintype "bidirectional"))
      (node (ref "SV101") (pin "31") (pinfunction "S_31") (pintype "passive"))
    )
    (net (code "90") (name "/{slash}SLTSL") (class "Default")
      (node (ref "IC107") (pin "20") (pinfunction "~{CS}_20") (pintype "input"))
      (node (ref "IC109") (pin "9") (pinfunction "I7_9") (pintype "input"))
      (node (ref "SLOT101") (pin "B2") (pinfunction "/SLTSL_B2") (pintype "bidirectional"))
    )
    (net (code "91") (name "/{slash}WAIT") (class "Default")
      (node (ref "SLOT101") (pin "A4") (pinfunction "/WAIT_A4") (pintype "bidirectional"))
      (node (ref "SV101") (pin "32") (pinfunction "S_32") (pintype "passive"))
    )
    (net (code "92") (name "/{slash}WE") (class "Default")
      (node (ref "IC107") (pin "27") (pinfunction "~{WE}_27") (pintype "input"))
      (node (ref "R103") (pin "2") (pinfunction "2_2") (pintype "passive"))
      (node (ref "S101") (pin "3") (pinfunction "S_3") (pintype "passive"))
    )
    (net (code "93") (name "/{slash}WEX") (class "Default")
      (node (ref "S101") (pin "2") (pinfunction "P_2") (pintype "passive"))
      (node (ref "SLOT101") (pin "A3") (pinfunction "NC0_A3") (pintype "bidirectional"))
    )
    (net (code "94") (name "/{slash}WR") (class "Default")
      (node (ref "IC102") (pin "2") (pinfunction "WR_2") (pintype "input"))
      (node (ref "IC103") (pin "2") (pinfunction "I0_2") (pintype "input"))
      (node (ref "IC109") (pin "7") (pinfunction "I5_7") (pintype "input"))
      (node (ref "SLOT101") (pin "A7") (pinfunction "/WR_A7") (pintype "bidirectional"))
    )
    (net (code "95") (name "/{slash}WR#") (class "Default")
      (node (ref "IC109") (pin "21") (pinfunction "O7_21") (pintype "bidirectional"))
      (node (ref "SV101") (pin "28") (pinfunction "S_28") (pintype "passive"))
    )
    (net (code "96") (name "GND") (class "Default")
      (node (ref "C101") (pin "1") (pinfunction "1_1") (pintype "passive"))
      (node (ref "C102") (pin "1") (pinfunction "1_1") (pintype "passive"))
      (node (ref "C103") (pin "1") (pinfunction "1_1") (pintype "passive"))
      (node (ref "C104") (pin "1") (pinfunction "1_1") (pintype "passive"))
      (node (ref "IC101") (pin "1") (pinfunction "DIR_1") (pintype "input"))
      (node (ref "IC101") (pin "10") (pinfunction "GND_10") (pintype "power_in"))
      (node (ref "IC101") (pin "19") (pinfunction "G_19") (pintype "input"))
      (node (ref "IC102") (pin "14") (pinfunction "GND_14") (pintype "power_in"))
      (node (ref "IC103") (pin "12") (pinfunction "GND_12") (pintype "power_in"))
      (node (ref "IC104") (pin "1") (pinfunction "DIR_1") (pintype "input"))
      (node (ref "IC104") (pin "10") (pinfunction "GND_10") (pintype "power_in"))
      (node (ref "IC104") (pin "11") (pinfunction "B8_11") (pintype "bidirectional"))
      (node (ref "IC104") (pin "12") (pinfunction "B7_12") (pintype "bidirectional"))
      (node (ref "IC104") (pin "13") (pinfunction "B6_13") (pintype "bidirectional"))
      (node (ref "IC104") (pin "14") (pinfunction "B5_14") (pintype "bidirectional"))
      (node (ref "IC104") (pin "15") (pinfunction "B4_15") (pintype "bidirectional"))
      (node (ref "IC104") (pin "16") (pinfunction "B3_16") (pintype "bidirectional"))
      (node (ref "IC105") (pin "12") (pinfunction "GND_12") (pintype "power_in"))
      (node (ref "IC106") (pin "10") (pinfunction "GND_10") (pintype "power_in"))
      (node (ref "IC106") (pin "19") (pinfunction "G_19") (pintype "input"))
      (node (ref "IC107") (pin "14") (pinfunction "VSS_14") (pintype "power_in"))
      (node (ref "IC108") (pin "7") (pinfunction "GND_7") (pintype "power_in"))
      (node (ref "IC109") (pin "12") (pinfunction "GND_12") (pintype "power_in"))
      (node (ref "IC110") (pin "1") (pinfunction "OC_1") (pintype "input"))
      (node (ref "IC110") (pin "10") (pinfunction "GND_10") (pintype "power_in"))
      (node (ref "LED101") (pin "K") (pinfunction "C_K") (pintype "passive"))
      (node (ref "LED103") (pin "K") (pinfunction "C_K") (pintype "passive"))
      (node (ref "SLOT101") (pin "A21") (pinfunction "GNDA_A21") (pintype "bidirectional"))
      (node (ref "SLOT101") (pin "A22") (pinfunction "GNDB_A22") (pintype "bidirectional"))
      (node (ref "SV101") (pin "33") (pinfunction "S_33") (pintype "passive"))
      (node (ref "SV101") (pin "34") (pinfunction "S_34") (pintype "passive"))
    )
    (net (code "97") (name "Net-(IC102A-SP{slash}EN)") (class "Default")
      (node (ref "IC102") (pin "16") (pinfunction "SP/EN_16") (pintype "bidirectional"))
      (node (ref "R101") (pin "1") (pinfunction "1_1") (pintype "passive"))
    )
    (net (code "98") (name "Net-(IC108A-I1)") (class "Default")
      (node (ref "IC108") (pin "2") (pinfunction "I1_2") (pintype "input"))
      (node (ref "IC108") (pin "6") (pinfunction "O_6") (pintype "output"))
    )
    (net (code "99") (name "Net-(IC108C-I0)") (class "Default")
      (node (ref "IC108") (pin "11") (pinfunction "O_11") (pintype "output"))
      (node (ref "IC108") (pin "9") (pinfunction "I0_9") (pintype "input"))
    )
    (net (code "100") (name "Net-(SLOT101-SW1)") (class "Default")
      (node (ref "SLOT101") (pin "B22") (pinfunction "SW1_B22") (pintype "bidirectional"))
      (node (ref "SLOT101") (pin "B23") (pinfunction "SW2_B23") (pintype "bidirectional"))
    )
    (net (code "101") (name "unconnected-(IC102A-CAS0-Pad12)") (class "Default")
      (node (ref "IC102") (pin "12") (pinfunction "CAS0_12") (pintype "bidirectional"))
    )
    (net (code "102") (name "unconnected-(IC102A-CAS1-Pad13)") (class "Default")
      (node (ref "IC102") (pin "13") (pinfunction "CAS1_13") (pintype "bidirectional"))
    )
    (net (code "103") (name "unconnected-(IC102A-CAS2-Pad15)") (class "Default")
      (node (ref "IC102") (pin "15") (pinfunction "CAS2_15") (pintype "bidirectional"))
    )
    (net (code "104") (name "unconnected-(IC105A-I10-Pad13)") (class "Default")
      (node (ref "IC105") (pin "13") (pinfunction "I10_13") (pintype "input"))
    )
    (net (code "105") (name "unconnected-(IC105A-O0-Pad14)") (class "Default")
      (node (ref "IC105") (pin "14") (pinfunction "O0_14") (pintype "bidirectional"))
    )
    (net (code "106") (name "unconnected-(S101-O-Pad1)") (class "Default")
      (node (ref "S101") (pin "1") (pinfunction "O_1") (pintype "passive"))
    )
    (net (code "107") (name "unconnected-(SLOT101-+12V-PadB24)") (class "Default")
      (node (ref "SLOT101") (pin "B24") (pinfunction "+12V_B24") (pintype "bidirectional"))
    )
    (net (code "108") (name "unconnected-(SLOT101--12V-PadB25)") (class "Default")
      (node (ref "SLOT101") (pin "B25") (pinfunction "-12V_B25") (pintype "bidirectional"))
    )
    (net (code "109") (name "unconnected-(SLOT101-NC1-PadB8)") (class "Default")
      (node (ref "SLOT101") (pin "B8") (pinfunction "NC1_B8") (pintype "bidirectional"))
    )
    (net (code "110") (name "unconnected-(SLOT101-SDIN-PadA25)") (class "Default")
      (node (ref "SLOT101") (pin "A25") (pinfunction "SDIN_A25") (pintype "bidirectional"))
    )
    (net (code "111") (name "unconnected-(SLOT101-{slash}CS2-PadB1)") (class "Default")
      (node (ref "SLOT101") (pin "B1") (pinfunction "/CS2_B1") (pintype "bidirectional"))
    )
    (net (code "112") (name "unconnected-(SLOT101-{slash}CS12-PadA2)") (class "Default")
      (node (ref "SLOT101") (pin "A2") (pinfunction "/CS12_A2") (pintype "bidirectional"))
    )
    (net (code "113") (name "unconnected-(SLOT101-{slash}MREQ-PadB6)") (class "Default")
      (node (ref "SLOT101") (pin "B6") (pinfunction "/MREQ_B6") (pintype "bidirectional"))
    )
    (net (code "114") (name "unconnected-(SLOT101-{slash}RFSH-PadB3)") (class "Default")
      (node (ref "SLOT101") (pin "B3") (pinfunction "/RFSH_B3") (pintype "bidirectional"))
    )
  )
)
